# HeaterCotrolPlusPIC.net
KiCad netlist of a schematic drawn in EAGLE
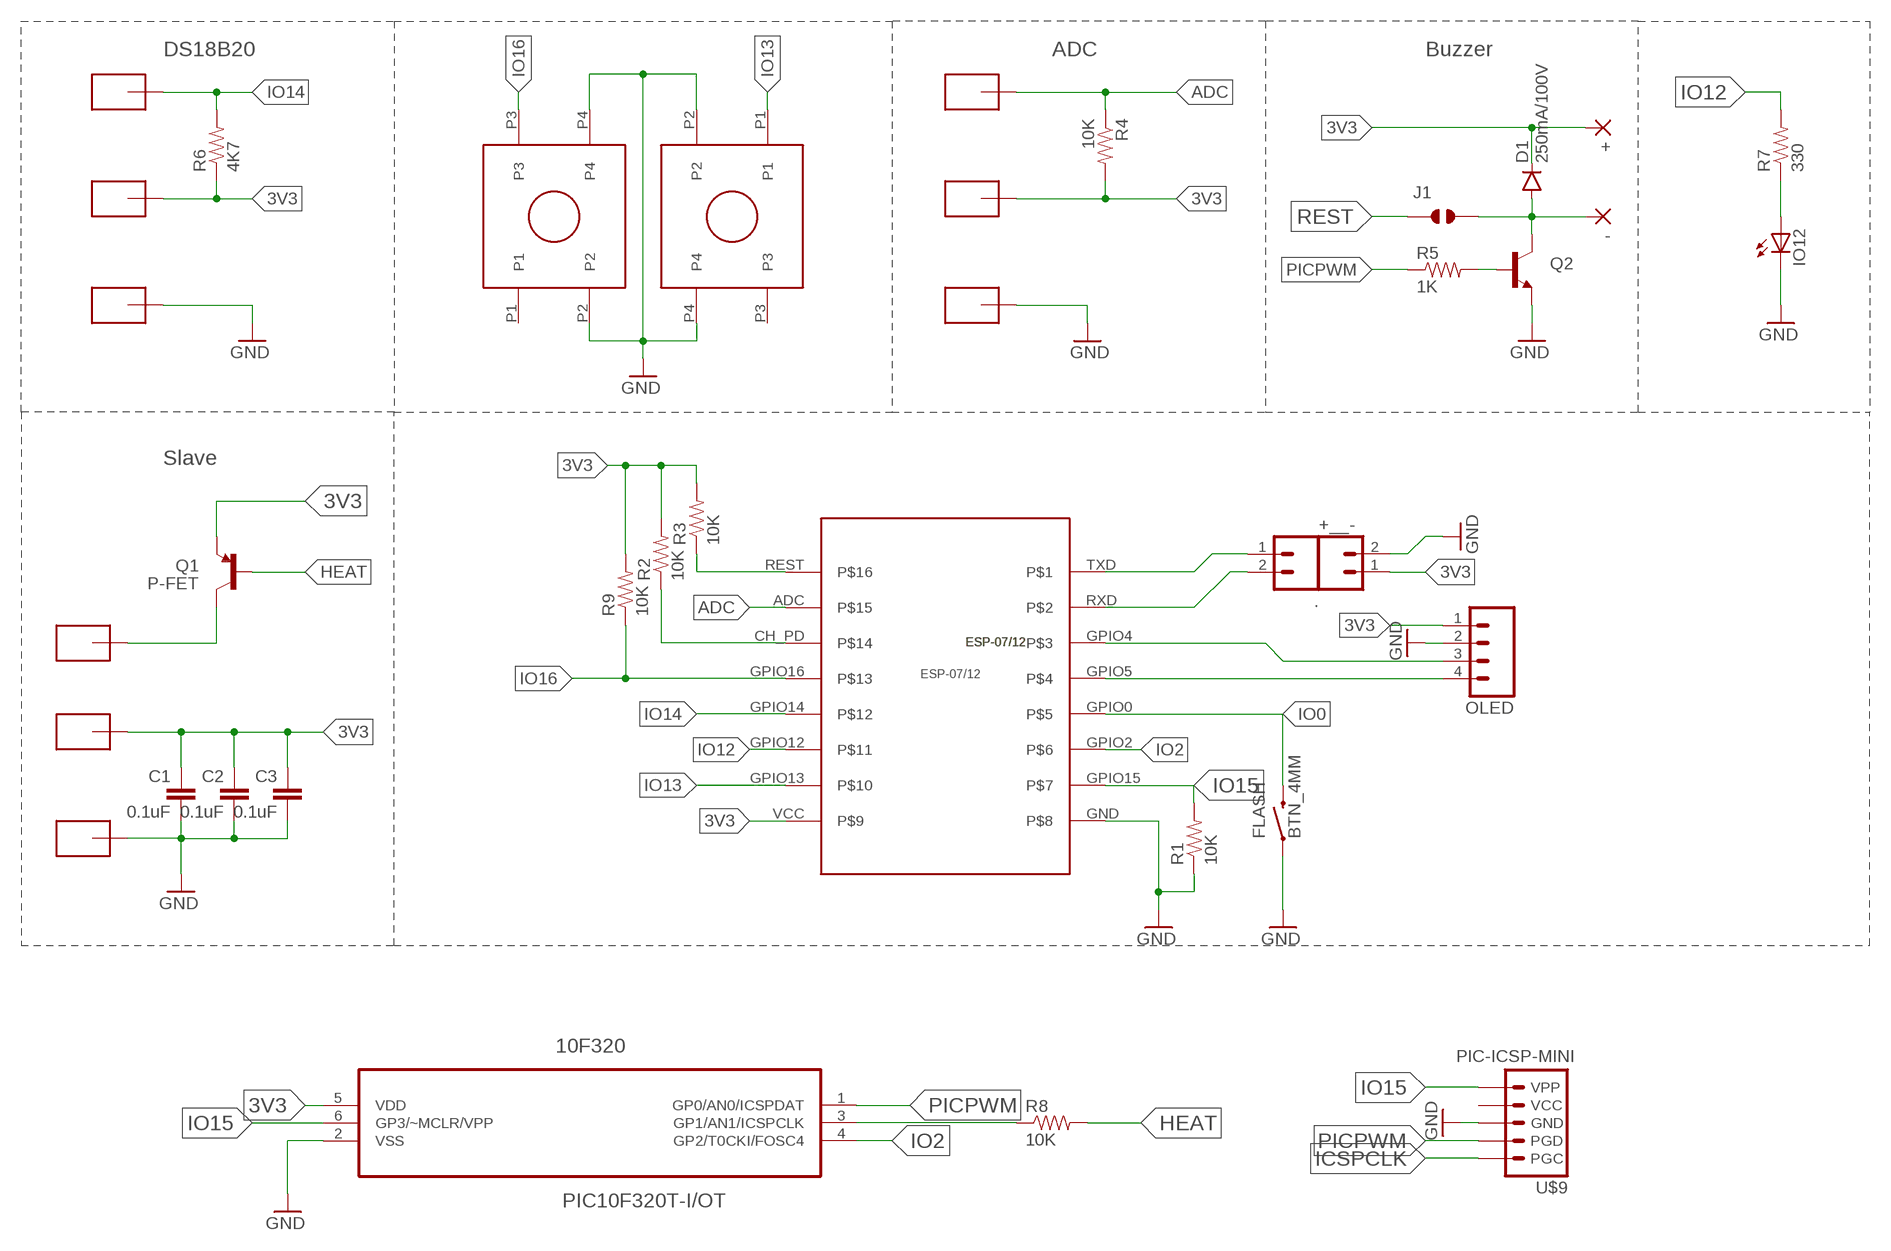
[diagram p0: schematic, sheet 1]

(export (version "E")
  (design (tool "Eeschema 10.0.6"))
  (components
    (comp (ref "+")
      (value "1,6/0,8")
      (footprint "eagle-import:1,6_0,8")
      (libsource (lib "eagle-import") (part "1,6/0,8"))
    )
    (comp (ref "+__-")
      (value "M02PTH")
      (footprint "eagle-import:1X02")
      (libsource (lib "eagle-import") (part "M02PTH"))
    )
    (comp (ref "-")
      (value "1,6/0,8")
      (footprint "eagle-import:1,6_0,8")
      (libsource (lib "eagle-import") (part "1,6/0,8"))
    )
    (comp (ref ".")
      (value "M02PTH")
      (footprint "eagle-import:1X02")
      (libsource (lib "eagle-import") (part "M02PTH"))
    )
    (comp (ref "10F320")
      (value "PIC10F320T-I/OT")
      (footprint "eagle-import:SOT95P270X145-6N")
      (fields (field (name "MPN") "PIC10F220T-I/OT"))
      (libsource (lib "eagle-import") (part "PIC10F220T-I/OT"))
    )
    (comp (ref "C1")
      (value "0.1uF")
      (footprint "eagle-import:0805-CAP")
      (libsource (lib "eagle-import") (part "CAP"))
    )
    (comp (ref "C2")
      (value "0.1uF")
      (footprint "eagle-import:0805-CAP")
      (libsource (lib "eagle-import") (part "CAP"))
    )
    (comp (ref "C3")
      (value "0.1uF")
      (footprint "eagle-import:0805-CAP")
      (libsource (lib "eagle-import") (part "CAP"))
    )
    (comp (ref "D1")
      (value "250mA/100V")
      (footprint "eagle-import:SOD-323")
      (libsource (lib "eagle-import") (part "DIODEBAS16"))
    )
    (comp (ref "FLASH")
      (value "BTN_4MM")
      (footprint "eagle-import:BTN_4MM")
      (libsource (lib "eagle-import") (part "BTN_4MM"))
    )
    (comp (ref "IO12")
      (value "LEDCHIP-LED0805")
      (footprint "eagle-import:CHIP-LED0805")
      (libsource (lib "eagle-import") (part "LEDCHIP-LED0805"))
    )
    (comp (ref "J1")
      (value "JUMPER_SOLDER_1X2")
      (footprint "eagle-import:JUMPER_SOLDER_1X2")
      (libsource (lib "eagle-import") (part "JUMPER_SOLDER_1X2"))
    )
    (comp (ref "LEFT")
      (value "OMROM_TH")
      (footprint "eagle-import:OMROM_TH")
      (libsource (lib "eagle-import") (part "OMROM_TH"))
    )
    (comp (ref "OLED")
      (value "M04PTH")
      (footprint "eagle-import:1X04")
      (libsource (lib "eagle-import") (part "M04PTH"))
    )
    (comp (ref "Q1")
      (value "P-FET")
      (footprint "eagle-import:SOT23-3")
      (libsource (lib "eagle-import") (part "TRANSISTOR_PNPSMD"))
    )
    (comp (ref "Q2")
      (value "TRANSISTOR_NPNSOT23-3")
      (footprint "eagle-import:SOT23-3")
      (libsource (lib "eagle-import") (part "TRANSISTOR_NPNSOT23-3"))
    )
    (comp (ref "R1")
      (value "10K")
      (footprint "eagle-import:0805")
      (libsource (lib "eagle-import") (part "RESISTOR0805-RES"))
    )
    (comp (ref "R2")
      (value "10K")
      (footprint "eagle-import:0805")
      (libsource (lib "eagle-import") (part "RESISTOR0805-RES"))
    )
    (comp (ref "R3")
      (value "10K")
      (footprint "eagle-import:0805")
      (libsource (lib "eagle-import") (part "RESISTOR0805-RES"))
    )
    (comp (ref "R4")
      (value "10K")
      (footprint "eagle-import:0805")
      (libsource (lib "eagle-import") (part "RESISTOR0805-RES"))
    )
    (comp (ref "R5")
      (value "1K")
      (footprint "eagle-import:0805")
      (libsource (lib "eagle-import") (part "RESISTOR0805-RES"))
    )
    (comp (ref "R6")
      (value "4K7")
      (footprint "eagle-import:0805")
      (libsource (lib "eagle-import") (part "RESISTOR0805-RES"))
    )
    (comp (ref "R7")
      (value "330")
      (footprint "eagle-import:0805")
      (libsource (lib "eagle-import") (part "RESISTOR0805-RES"))
    )
    (comp (ref "R8")
      (value "10K")
      (footprint "eagle-import:0805")
      (libsource (lib "eagle-import") (part "RESISTOR0805-RES"))
    )
    (comp (ref "R9")
      (value "10K")
      (footprint "eagle-import:0805")
      (libsource (lib "eagle-import") (part "RESISTOR0805-RES"))
    )
    (comp (ref "RIGHT")
      (value "OMROM_TH")
      (footprint "eagle-import:OMROM_TH")
      (libsource (lib "eagle-import") (part "OMROM_TH"))
    )
    (comp (ref "U$1")
      (value "ESP-07/12")
      (footprint "eagle-import:ESP-07_12")
      (libsource (lib "eagle-import") (part "ESP-07/12"))
    )
    (comp (ref "U$2")
      (value "SMD-PAD1")
      (footprint "eagle-import:SMD-PAD1")
      (libsource (lib "eagle-import") (part "SMD-PAD1"))
    )
    (comp (ref "U$3")
      (value "SMD-PAD1")
      (footprint "eagle-import:SMD-PAD1")
      (libsource (lib "eagle-import") (part "SMD-PAD1"))
    )
    (comp (ref "U$4")
      (value "SMD-PAD1")
      (footprint "eagle-import:SMD-PAD1")
      (libsource (lib "eagle-import") (part "SMD-PAD1"))
    )
    (comp (ref "U$5")
      (value "SMD-PAD1")
      (footprint "eagle-import:SMD-PAD1")
      (libsource (lib "eagle-import") (part "SMD-PAD1"))
    )
    (comp (ref "U$6")
      (value "SMD-PAD1")
      (footprint "eagle-import:SMD-PAD1")
      (libsource (lib "eagle-import") (part "SMD-PAD1"))
    )
    (comp (ref "U$7")
      (value "SMD-PAD1")
      (footprint "eagle-import:SMD-PAD1")
      (libsource (lib "eagle-import") (part "SMD-PAD1"))
    )
    (comp (ref "U$8")
      (value "SMD-PAD1")
      (footprint "eagle-import:SMD-PAD1")
      (libsource (lib "eagle-import") (part "SMD-PAD1"))
    )
    (comp (ref "U$9")
      (value "PIC-ICSP-MINI")
      (footprint "eagle-import:PIC-ICSP-MINI")
      (libsource (lib "eagle-import") (part "PIC-ICSP-MINI"))
    )
    (comp (ref "U$10")
      (value "SMD-PAD1")
      (footprint "eagle-import:SMD-PAD1")
      (libsource (lib "eagle-import") (part "SMD-PAD1"))
    )
    (comp (ref "U$11")
      (value "SMD-PAD1")
      (footprint "eagle-import:SMD-PAD1")
      (libsource (lib "eagle-import") (part "SMD-PAD1"))
    )
  )
  (nets
    (net (code "1") (name "3V3") (class "Default")
      (node (ref "+") (pin "1") (pinfunction "P_1") (pintype "passive"))
      (node (ref "+__-") (pin "1") (pinfunction "1_1") (pintype "passive"))
      (node (ref "10F320") (pin "5") (pinfunction "VDD_5") (pintype "power_in"))
      (node (ref "C1") (pin "1") (pinfunction "1_1") (pintype "passive"))
      (node (ref "C2") (pin "1") (pinfunction "1_1") (pintype "passive"))
      (node (ref "C3") (pin "1") (pinfunction "1_1") (pintype "passive"))
      (node (ref "D1") (pin "C") (pinfunction "C_C") (pintype "passive"))
      (node (ref "OLED") (pin "1") (pinfunction "1_1") (pintype "passive"))
      (node (ref "Q1") (pin "2") (pinfunction "E_2") (pintype "passive"))
      (node (ref "R2") (pin "2") (pinfunction "2_2") (pintype "passive"))
      (node (ref "R3") (pin "2") (pinfunction "2_2") (pintype "passive"))
      (node (ref "R4") (pin "2") (pinfunction "2_2") (pintype "passive"))
      (node (ref "R6") (pin "1") (pinfunction "1_1") (pintype "passive"))
      (node (ref "R9") (pin "2") (pinfunction "2_2") (pintype "passive"))
      (node (ref "U$1") (pin "VCC") (pinfunction "P$9_VCC") (pintype "bidirectional"))
      (node (ref "U$3") (pin ">NAME") (pinfunction "P$1_>NAME") (pintype "bidirectional"))
      (node (ref "U$4") (pin ">NAME") (pinfunction "P$1_>NAME") (pintype "bidirectional"))
      (node (ref "U$8") (pin ">NAME") (pinfunction "P$1_>NAME") (pintype "bidirectional"))
    )
    (net (code "2") (name "ADC") (class "Default")
      (node (ref "R4") (pin "1") (pinfunction "1_1") (pintype "passive"))
      (node (ref "U$1") (pin "ADC") (pinfunction "P$15_ADC") (pintype "bidirectional"))
      (node (ref "U$7") (pin ">NAME") (pinfunction "P$1_>NAME") (pintype "bidirectional"))
    )
    (net (code "3") (name "GND") (class "Default")
      (node (ref "+__-") (pin "2") (pinfunction "2_2") (pintype "passive"))
      (node (ref "10F320") (pin "2") (pinfunction "VSS_2") (pintype "power_in"))
      (node (ref "C1") (pin "2") (pinfunction "2_2") (pintype "passive"))
      (node (ref "C2") (pin "2") (pinfunction "2_2") (pintype "passive"))
      (node (ref "C3") (pin "2") (pinfunction "2_2") (pintype "passive"))
      (node (ref "FLASH") (pin "1") (pinfunction "1_1") (pintype "passive"))
      (node (ref "IO12") (pin "C") (pinfunction "C_C") (pintype "passive"))
      (node (ref "LEFT") (pin "P2") (pinfunction "P2_P2") (pintype "bidirectional"))
      (node (ref "LEFT") (pin "P4") (pinfunction "P4_P4") (pintype "bidirectional"))
      (node (ref "OLED") (pin "2") (pinfunction "2_2") (pintype "passive"))
      (node (ref "Q2") (pin "2") (pinfunction "E_2") (pintype "passive"))
      (node (ref "R1") (pin "1") (pinfunction "1_1") (pintype "passive"))
      (node (ref "RIGHT") (pin "P2") (pinfunction "P2_P2") (pintype "bidirectional"))
      (node (ref "RIGHT") (pin "P4") (pinfunction "P4_P4") (pintype "bidirectional"))
      (node (ref "U$1") (pin "GND") (pinfunction "P$8_GND") (pintype "bidirectional"))
      (node (ref "U$11") (pin ">NAME") (pinfunction "P$1_>NAME") (pintype "bidirectional"))
      (node (ref "U$5") (pin ">NAME") (pinfunction "P$1_>NAME") (pintype "bidirectional"))
      (node (ref "U$6") (pin ">NAME") (pinfunction "P$1_>NAME") (pintype "bidirectional"))
      (node (ref "U$9") (pin "3") (pinfunction "GND_3") (pintype "passive"))
    )
    (net (code "4") (name "HEAT") (class "Default")
      (node (ref "Q1") (pin "1") (pinfunction "B_1") (pintype "passive"))
      (node (ref "R8") (pin "2") (pinfunction "2_2") (pintype "passive"))
    )
    (net (code "5") (name "ICSPCLK") (class "Default")
      (node (ref "10F320") (pin "3") (pinfunction "GP1/AN1/ICSPCLK_3") (pintype "bidirectional"))
      (node (ref "R8") (pin "1") (pinfunction "1_1") (pintype "passive"))
      (node (ref "U$9") (pin "5") (pinfunction "PGC_5") (pintype "passive"))
    )
    (net (code "6") (name "IO0") (class "Default")
      (node (ref "FLASH") (pin "2") (pinfunction "2_2") (pintype "passive"))
      (node (ref "U$1") (pin "GPIO0") (pinfunction "P$5_GPIO0") (pintype "bidirectional"))
    )
    (net (code "7") (name "IO2") (class "Default")
      (node (ref "10F320") (pin "4") (pinfunction "GP2/T0CKI/FOSC4_4") (pintype "bidirectional"))
      (node (ref "U$1") (pin "GPIO2") (pinfunction "P$6_GPIO2") (pintype "bidirectional"))
    )
    (net (code "8") (name "IO12") (class "Default")
      (node (ref "R7") (pin "2") (pinfunction "2_2") (pintype "passive"))
      (node (ref "U$1") (pin "GPIO12") (pinfunction "P$11_GPIO12") (pintype "bidirectional"))
    )
    (net (code "9") (name "IO13") (class "Default")
      (node (ref "RIGHT") (pin "P1") (pinfunction "P1_P1") (pintype "bidirectional"))
      (node (ref "U$1") (pin "GPIO13") (pinfunction "P$10_GPIO13") (pintype "bidirectional"))
    )
    (net (code "10") (name "IO14") (class "Default")
      (node (ref "R6") (pin "2") (pinfunction "2_2") (pintype "passive"))
      (node (ref "U$1") (pin "GPIO14") (pinfunction "P$12_GPIO14") (pintype "bidirectional"))
      (node (ref "U$10") (pin ">NAME") (pinfunction "P$1_>NAME") (pintype "bidirectional"))
    )
    (net (code "11") (name "IO15") (class "Default")
      (node (ref "10F320") (pin "6") (pinfunction "GP3/~{MCLR/VPP}_6") (pintype "input"))
      (node (ref "R1") (pin "2") (pinfunction "2_2") (pintype "passive"))
      (node (ref "U$1") (pin "GPIO15") (pinfunction "P$7_GPIO15") (pintype "bidirectional"))
      (node (ref "U$9") (pin "1") (pinfunction "VPP_1") (pintype "passive"))
    )
    (net (code "12") (name "IO16") (class "Default")
      (node (ref "LEFT") (pin "P3") (pinfunction "P3_P3") (pintype "bidirectional"))
      (node (ref "R9") (pin "1") (pinfunction "1_1") (pintype "passive"))
      (node (ref "U$1") (pin "GPIO16") (pinfunction "P$13_GPIO16") (pintype "bidirectional"))
    )
    (net (code "13") (name "Net-(--P)") (class "Default")
      (node (ref "-") (pin "1") (pinfunction "P_1") (pintype "passive"))
      (node (ref "D1") (pin "A") (pinfunction "A_A") (pintype "passive"))
      (node (ref "J1") (pin "2") (pinfunction "2_2") (pintype "passive"))
      (node (ref "Q2") (pin "3") (pinfunction "C_3") (pintype "passive"))
    )
    (net (code "14") (name "Net-(IO12-PadA)") (class "Default")
      (node (ref "IO12") (pin "A") (pinfunction "A_A") (pintype "passive"))
      (node (ref "R7") (pin "1") (pinfunction "1_1") (pintype "passive"))
    )
    (net (code "15") (name "Net-(Q1-C)") (class "Default")
      (node (ref "Q1") (pin "3") (pinfunction "C_3") (pintype "passive"))
      (node (ref "U$2") (pin ">NAME") (pinfunction "P$1_>NAME") (pintype "bidirectional"))
    )
    (net (code "16") (name "Net-(Q2-B)") (class "Default")
      (node (ref "Q2") (pin "1") (pinfunction "B_1") (pintype "passive"))
      (node (ref "R5") (pin "2") (pinfunction "2_2") (pintype "passive"))
    )
    (net (code "17") (name "Net-(U$1-P$1)") (class "Default")
      (node (ref ".") (pin "1") (pinfunction "1_1") (pintype "passive"))
      (node (ref "U$1") (pin "TXD") (pinfunction "P$1_TXD") (pintype "bidirectional"))
    )
    (net (code "18") (name "Net-(U$1-P$2)") (class "Default")
      (node (ref ".") (pin "2") (pinfunction "2_2") (pintype "passive"))
      (node (ref "U$1") (pin "RXD") (pinfunction "P$2_RXD") (pintype "bidirectional"))
    )
    (net (code "19") (name "Net-(U$1-P$3)") (class "Default")
      (node (ref "OLED") (pin "3") (pinfunction "3_3") (pintype "passive"))
      (node (ref "U$1") (pin "GPIO4") (pinfunction "P$3_GPIO4") (pintype "bidirectional"))
    )
    (net (code "20") (name "Net-(U$1-P$4)") (class "Default")
      (node (ref "OLED") (pin "4") (pinfunction "4_4") (pintype "passive"))
      (node (ref "U$1") (pin "GPIO5") (pinfunction "P$4_GPIO5") (pintype "bidirectional"))
    )
    (net (code "21") (name "Net-(U$1-P$14)") (class "Default")
      (node (ref "R2") (pin "1") (pinfunction "1_1") (pintype "passive"))
      (node (ref "U$1") (pin "CH_PD") (pinfunction "P$14_CH_PD") (pintype "bidirectional"))
    )
    (net (code "22") (name "PICPWM") (class "Default")
      (node (ref "10F320") (pin "1") (pinfunction "GP0/AN0/ICSPDAT_1") (pintype "bidirectional"))
      (node (ref "R5") (pin "1") (pinfunction "1_1") (pintype "passive"))
      (node (ref "U$9") (pin "4") (pinfunction "PGD_4") (pintype "passive"))
    )
    (net (code "23") (name "REST") (class "Default")
      (node (ref "J1") (pin "1") (pinfunction "1_1") (pintype "passive"))
      (node (ref "R3") (pin "1") (pinfunction "1_1") (pintype "passive"))
      (node (ref "U$1") (pin "REST") (pinfunction "P$16_REST") (pintype "bidirectional"))
    )
    (net (code "24") (name "unconnected-(LEFT-PadP1)") (class "Default")
      (node (ref "LEFT") (pin "P1") (pinfunction "P1_P1") (pintype "bidirectional"))
    )
    (net (code "25") (name "unconnected-(RIGHT-PadP3)") (class "Default")
      (node (ref "RIGHT") (pin "P3") (pinfunction "P3_P3") (pintype "bidirectional"))
    )
    (net (code "26") (name "unconnected-(U$9-VCC-Pad2)") (class "Default")
      (node (ref "U$9") (pin "2") (pinfunction "VCC_2") (pintype "passive"))
    )
  )
)
